# motorthing-v2smd.net
KiCad netlist of a schematic drawn in EAGLE
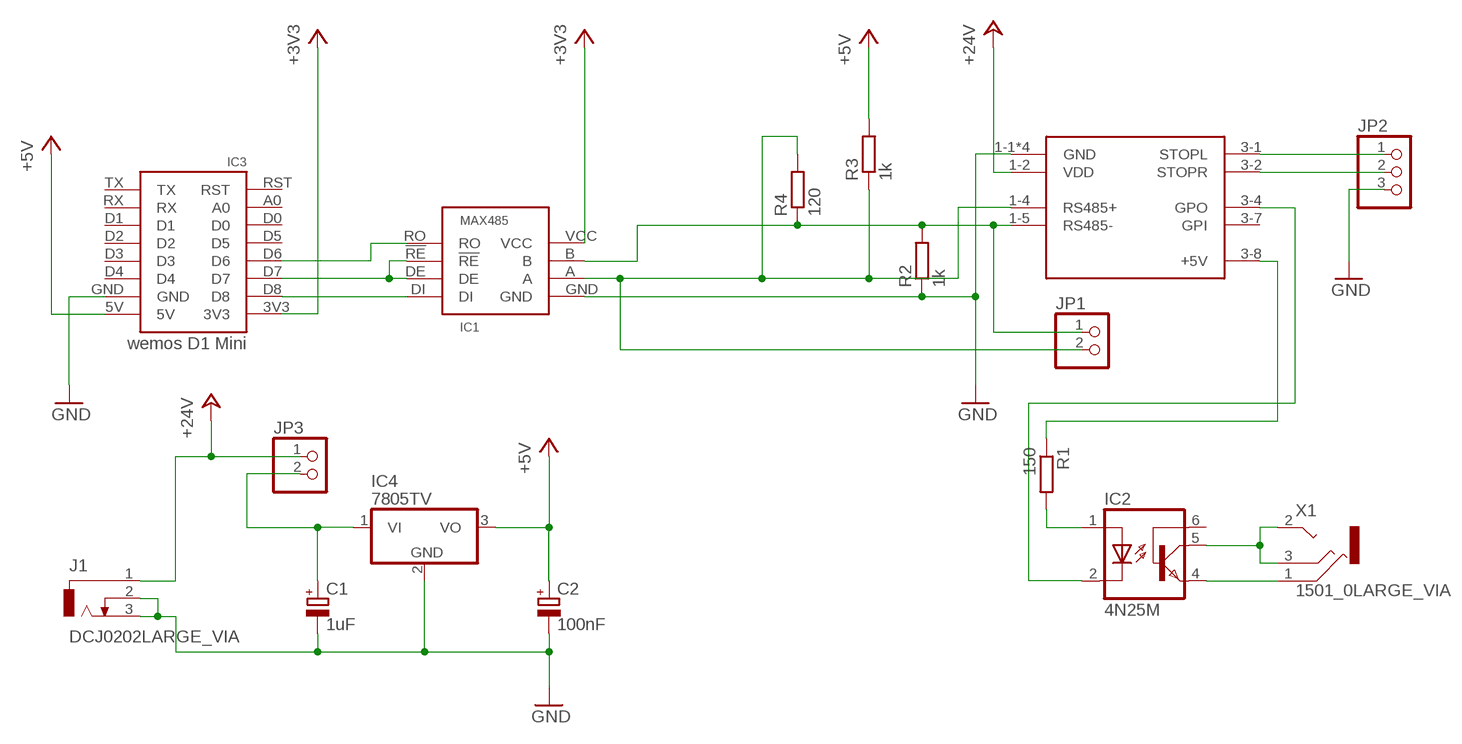
[diagram p0: schematic, sheet 1]

(export (version "E")
  (design (tool "Eeschema 10.0.6"))
  (components
    (comp (ref "C1")
      (value "1uF")
      (footprint "eagle-import:TT2D6")
      (libsource (lib "eagle-import") (part "CPOL-EUTT2D6"))
    )
    (comp (ref "C2")
      (value "100nF")
      (footprint "eagle-import:TT2D5")
      (libsource (lib "eagle-import") (part "CPOL-EUTT2D5"))
    )
    (comp (ref "IC1")
      (value "MAX485")
      (footprint "eagle-import:DIL08")
      (libsource (lib "eagle-import") (part "MAX485"))
    )
    (comp (ref "IC2")
      (value "4N25M")
      (footprint "eagle-import:DIL06")
      (fields (field (name "MPN") "4N25-M"))
      (libsource (lib "eagle-import") (part "4N?M25"))
    )
    (comp (ref "IC3")
      (value "wemos D1 Mini")
      (footprint "eagle-import:WEMOS-NOSILK")
      (libsource (lib "eagle-import") (part "WEMOSNOSILK"))
    )
    (comp (ref "IC4")
      (value "7805TV")
      (footprint "eagle-import:TO220V")
      (libsource (lib "eagle-import") (part "78TV05"))
    )
    (comp (ref "J1")
      (value "DCJ0202LARGE_VIA")
      (footprint "eagle-import:DCJ0202_LV")
      (libsource (lib "eagle-import") (part "DCJ0202LARGE_VIA"))
    )
    (comp (ref "JP1")
      (value "PINHD-1X2")
      (footprint "eagle-import:1X02")
      (libsource (lib "eagle-import") (part "PINHD-1X2"))
    )
    (comp (ref "JP2")
      (value "PINHD-1X3")
      (footprint "eagle-import:1X03")
      (libsource (lib "eagle-import") (part "PINHD-1X3"))
    )
    (comp (ref "JP3")
      (value "PINHD-1X2")
      (footprint "eagle-import:1X02")
      (libsource (lib "eagle-import") (part "PINHD-1X2"))
    )
    (comp (ref "R1")
      (value "150")
      (footprint "eagle-import:0207_10")
      (libsource (lib "eagle-import") (part "R-EU_0207/10"))
    )
    (comp (ref "R2")
      (value "1k")
      (footprint "eagle-import:0207_10")
      (libsource (lib "eagle-import") (part "R-EU_0207/10"))
    )
    (comp (ref "R3")
      (value "1k")
      (footprint "eagle-import:0207_10")
      (libsource (lib "eagle-import") (part "R-EU_0207/10"))
    )
    (comp (ref "R4")
      (value "120")
      (footprint "eagle-import:0207_10")
      (libsource (lib "eagle-import") (part "R-EU_0207/10"))
    )
    (comp (ref "TMCM-110")
      (value "TMCM-110SMD")
      (footprint "eagle-import:TMCM-110_SMD")
      (libsource (lib "eagle-import") (part "TMCM-110SMD"))
    )
    (comp (ref "X1")
      (value "1501_0LARGE_VIA")
      (footprint "eagle-import:1501_05_LV")
      (libsource (lib "eagle-import") (part "1501_0LARGE_VIA"))
    )
  )
  (nets
    (net (code "1") (name "+3V3") (class "Default")
      (node (ref "IC1") (pin "VCC") (pinfunction "VCC_VCC") (pintype "bidirectional"))
      (node (ref "IC3") (pin "3V3") (pinfunction "3V3_3V3") (pintype "bidirectional"))
    )
    (net (code "2") (name "+5V") (class "Default")
      (node (ref "C2") (pin "+") (pinfunction "+_+") (pintype "passive"))
      (node (ref "IC3") (pin "5V") (pinfunction "5V_5V") (pintype "bidirectional"))
      (node (ref "IC4") (pin "3") (pinfunction "VO_3") (pintype "passive"))
      (node (ref "R3") (pin "2") (pinfunction "2_2") (pintype "passive"))
    )
    (net (code "3") (name "+24V") (class "Default")
      (node (ref "J1") (pin "1") (pinfunction "1_1") (pintype "passive"))
      (node (ref "JP3") (pin "1") (pinfunction "1_1") (pintype "passive"))
      (node (ref "TMCM-110") (pin "1-2") (pinfunction "VDD_1-2") (pintype "bidirectional"))
    )
    (net (code "4") (name "GND") (class "Default")
      (node (ref "C1") (pin "-") (pinfunction "-_-") (pintype "passive"))
      (node (ref "C2") (pin "-") (pinfunction "-_-") (pintype "passive"))
      (node (ref "IC1") (pin "GND") (pinfunction "GND_GND") (pintype "bidirectional"))
      (node (ref "IC3") (pin "GND") (pinfunction "GND_GND") (pintype "bidirectional"))
      (node (ref "IC4") (pin "2") (pinfunction "GND_2") (pintype "passive"))
      (node (ref "J1") (pin "2") (pinfunction "2_2") (pintype "passive"))
      (node (ref "J1") (pin "3") (pinfunction "3_3") (pintype "passive"))
      (node (ref "JP2") (pin "3") (pinfunction "3_3") (pintype "passive"))
      (node (ref "R2") (pin "1") (pinfunction "1_1") (pintype "passive"))
      (node (ref "TMCM-110") (pin "1-1") (pinfunction "GND_1-1") (pintype "bidirectional"))
      (node (ref "TMCM-110") (pin "1-3") (pinfunction "GND_1-3") (pintype "bidirectional"))
      (node (ref "TMCM-110") (pin "3-3") (pinfunction "GND_3-3") (pintype "bidirectional"))
      (node (ref "TMCM-110") (pin "3-6") (pinfunction "GND_3-6") (pintype "bidirectional"))
    )
    (net (code "5") (name "Net-(IC1-PadDI)") (class "Default")
      (node (ref "IC1") (pin "DI") (pinfunction "DI_DI") (pintype "bidirectional"))
      (node (ref "IC3") (pin "D8") (pinfunction "D8_D8") (pintype "bidirectional"))
    )
    (net (code "6") (name "Net-(IC1-PadRO)") (class "Default")
      (node (ref "IC1") (pin "RO") (pinfunction "RO_RO") (pintype "bidirectional"))
      (node (ref "IC3") (pin "D6") (pinfunction "D6_D6") (pintype "bidirectional"))
    )
    (net (code "7") (name "Net-(IC1-~{RE})") (class "Default")
      (node (ref "IC1") (pin "!RE") (pinfunction "~{RE}_!RE") (pintype "bidirectional"))
      (node (ref "IC1") (pin "DE") (pinfunction "DE_DE") (pintype "bidirectional"))
      (node (ref "IC3") (pin "D7") (pinfunction "D7_D7") (pintype "bidirectional"))
    )
    (net (code "8") (name "Net-(IC2-A)") (class "Default")
      (node (ref "IC2") (pin "1") (pinfunction "A_1") (pintype "passive"))
      (node (ref "R1") (pin "2") (pinfunction "2_2") (pintype "passive"))
    )
    (net (code "9") (name "Net-(IC2-C)") (class "Default")
      (node (ref "IC2") (pin "2") (pinfunction "C_2") (pintype "passive"))
      (node (ref "TMCM-110") (pin "3-4") (pinfunction "GPO_3-4") (pintype "bidirectional"))
    )
    (net (code "10") (name "Net-(IC2-COL)") (class "Default")
      (node (ref "IC2") (pin "5") (pinfunction "COL_5") (pintype "passive"))
      (node (ref "X1") (pin "2") (pinfunction "2_2") (pintype "passive"))
      (node (ref "X1") (pin "3") (pinfunction "3_3") (pintype "passive"))
    )
    (net (code "11") (name "Net-(IC2-EMI)") (class "Default")
      (node (ref "IC2") (pin "4") (pinfunction "EMI_4") (pintype "passive"))
      (node (ref "X1") (pin "1") (pinfunction "1_1") (pintype "passive"))
    )
    (net (code "12") (name "Net-(IC4-VI)") (class "Default")
      (node (ref "C1") (pin "+") (pinfunction "+_+") (pintype "passive"))
      (node (ref "IC4") (pin "1") (pinfunction "VI_1") (pintype "input"))
      (node (ref "JP3") (pin "2") (pinfunction "2_2") (pintype "passive"))
    )
    (net (code "13") (name "Net-(TMCM-110-+5V)") (class "Default")
      (node (ref "R1") (pin "1") (pinfunction "1_1") (pintype "passive"))
      (node (ref "TMCM-110") (pin "3-8") (pinfunction "+5V_3-8") (pintype "bidirectional"))
    )
    (net (code "14") (name "Net-(TMCM-110-RS485+)") (class "Default")
      (node (ref "IC1") (pin "A") (pinfunction "A_A") (pintype "bidirectional"))
      (node (ref "JP1") (pin "2") (pinfunction "2_2") (pintype "passive"))
      (node (ref "R3") (pin "1") (pinfunction "1_1") (pintype "passive"))
      (node (ref "R4") (pin "2") (pinfunction "2_2") (pintype "passive"))
      (node (ref "TMCM-110") (pin "1-4") (pinfunction "RS485+_1-4") (pintype "bidirectional"))
    )
    (net (code "15") (name "Net-(TMCM-110-RS485-)") (class "Default")
      (node (ref "IC1") (pin "B") (pinfunction "B_B") (pintype "bidirectional"))
      (node (ref "JP1") (pin "1") (pinfunction "1_1") (pintype "passive"))
      (node (ref "R2") (pin "2") (pinfunction "2_2") (pintype "passive"))
      (node (ref "R4") (pin "1") (pinfunction "1_1") (pintype "passive"))
      (node (ref "TMCM-110") (pin "1-5") (pinfunction "RS485-_1-5") (pintype "bidirectional"))
    )
    (net (code "16") (name "Net-(TMCM-110-STOPL)") (class "Default")
      (node (ref "JP2") (pin "1") (pinfunction "1_1") (pintype "passive"))
      (node (ref "TMCM-110") (pin "3-1") (pinfunction "STOPL_3-1") (pintype "bidirectional"))
    )
    (net (code "17") (name "Net-(TMCM-110-STOPR)") (class "Default")
      (node (ref "JP2") (pin "2") (pinfunction "2_2") (pintype "passive"))
      (node (ref "TMCM-110") (pin "3-2") (pinfunction "STOPR_3-2") (pintype "bidirectional"))
    )
    (net (code "18") (name "unconnected-(IC2-BAS-Pad6)") (class "Default")
      (node (ref "IC2") (pin "6") (pinfunction "BAS_6") (pintype "passive"))
    )
    (net (code "19") (name "unconnected-(IC3-PadA0)") (class "Default")
      (node (ref "IC3") (pin "A0") (pinfunction "A0_A0") (pintype "bidirectional"))
    )
    (net (code "20") (name "unconnected-(IC3-PadD0)") (class "Default")
      (node (ref "IC3") (pin "D0") (pinfunction "D0_D0") (pintype "bidirectional"))
    )
    (net (code "21") (name "unconnected-(IC3-PadD1)") (class "Default")
      (node (ref "IC3") (pin "D1") (pinfunction "D1_D1") (pintype "bidirectional"))
    )
    (net (code "22") (name "unconnected-(IC3-PadD2)") (class "Default")
      (node (ref "IC3") (pin "D2") (pinfunction "D2_D2") (pintype "bidirectional"))
    )
    (net (code "23") (name "unconnected-(IC3-PadD3)") (class "Default")
      (node (ref "IC3") (pin "D3") (pinfunction "D3_D3") (pintype "bidirectional"))
    )
    (net (code "24") (name "unconnected-(IC3-PadD4)") (class "Default")
      (node (ref "IC3") (pin "D4") (pinfunction "D4_D4") (pintype "bidirectional"))
    )
    (net (code "25") (name "unconnected-(IC3-PadD5)") (class "Default")
      (node (ref "IC3") (pin "D5") (pinfunction "D5_D5") (pintype "bidirectional"))
    )
    (net (code "26") (name "unconnected-(IC3-PadRST)") (class "Default")
      (node (ref "IC3") (pin "RST") (pinfunction "RST_RST") (pintype "bidirectional"))
    )
    (net (code "27") (name "unconnected-(IC3-PadRX)") (class "Default")
      (node (ref "IC3") (pin "RX") (pinfunction "RX_RX") (pintype "bidirectional"))
    )
    (net (code "28") (name "unconnected-(IC3-PadTX)") (class "Default")
      (node (ref "IC3") (pin "TX") (pinfunction "TX_TX") (pintype "bidirectional"))
    )
    (net (code "29") (name "unconnected-(TMCM-110-GPI-Pad3-7)") (class "Default")
      (node (ref "TMCM-110") (pin "3-7") (pinfunction "GPI_3-7") (pintype "bidirectional"))
    )
  )
)
